# PowerBoard.net
KiCad netlist of a schematic drawn in Altium Designer
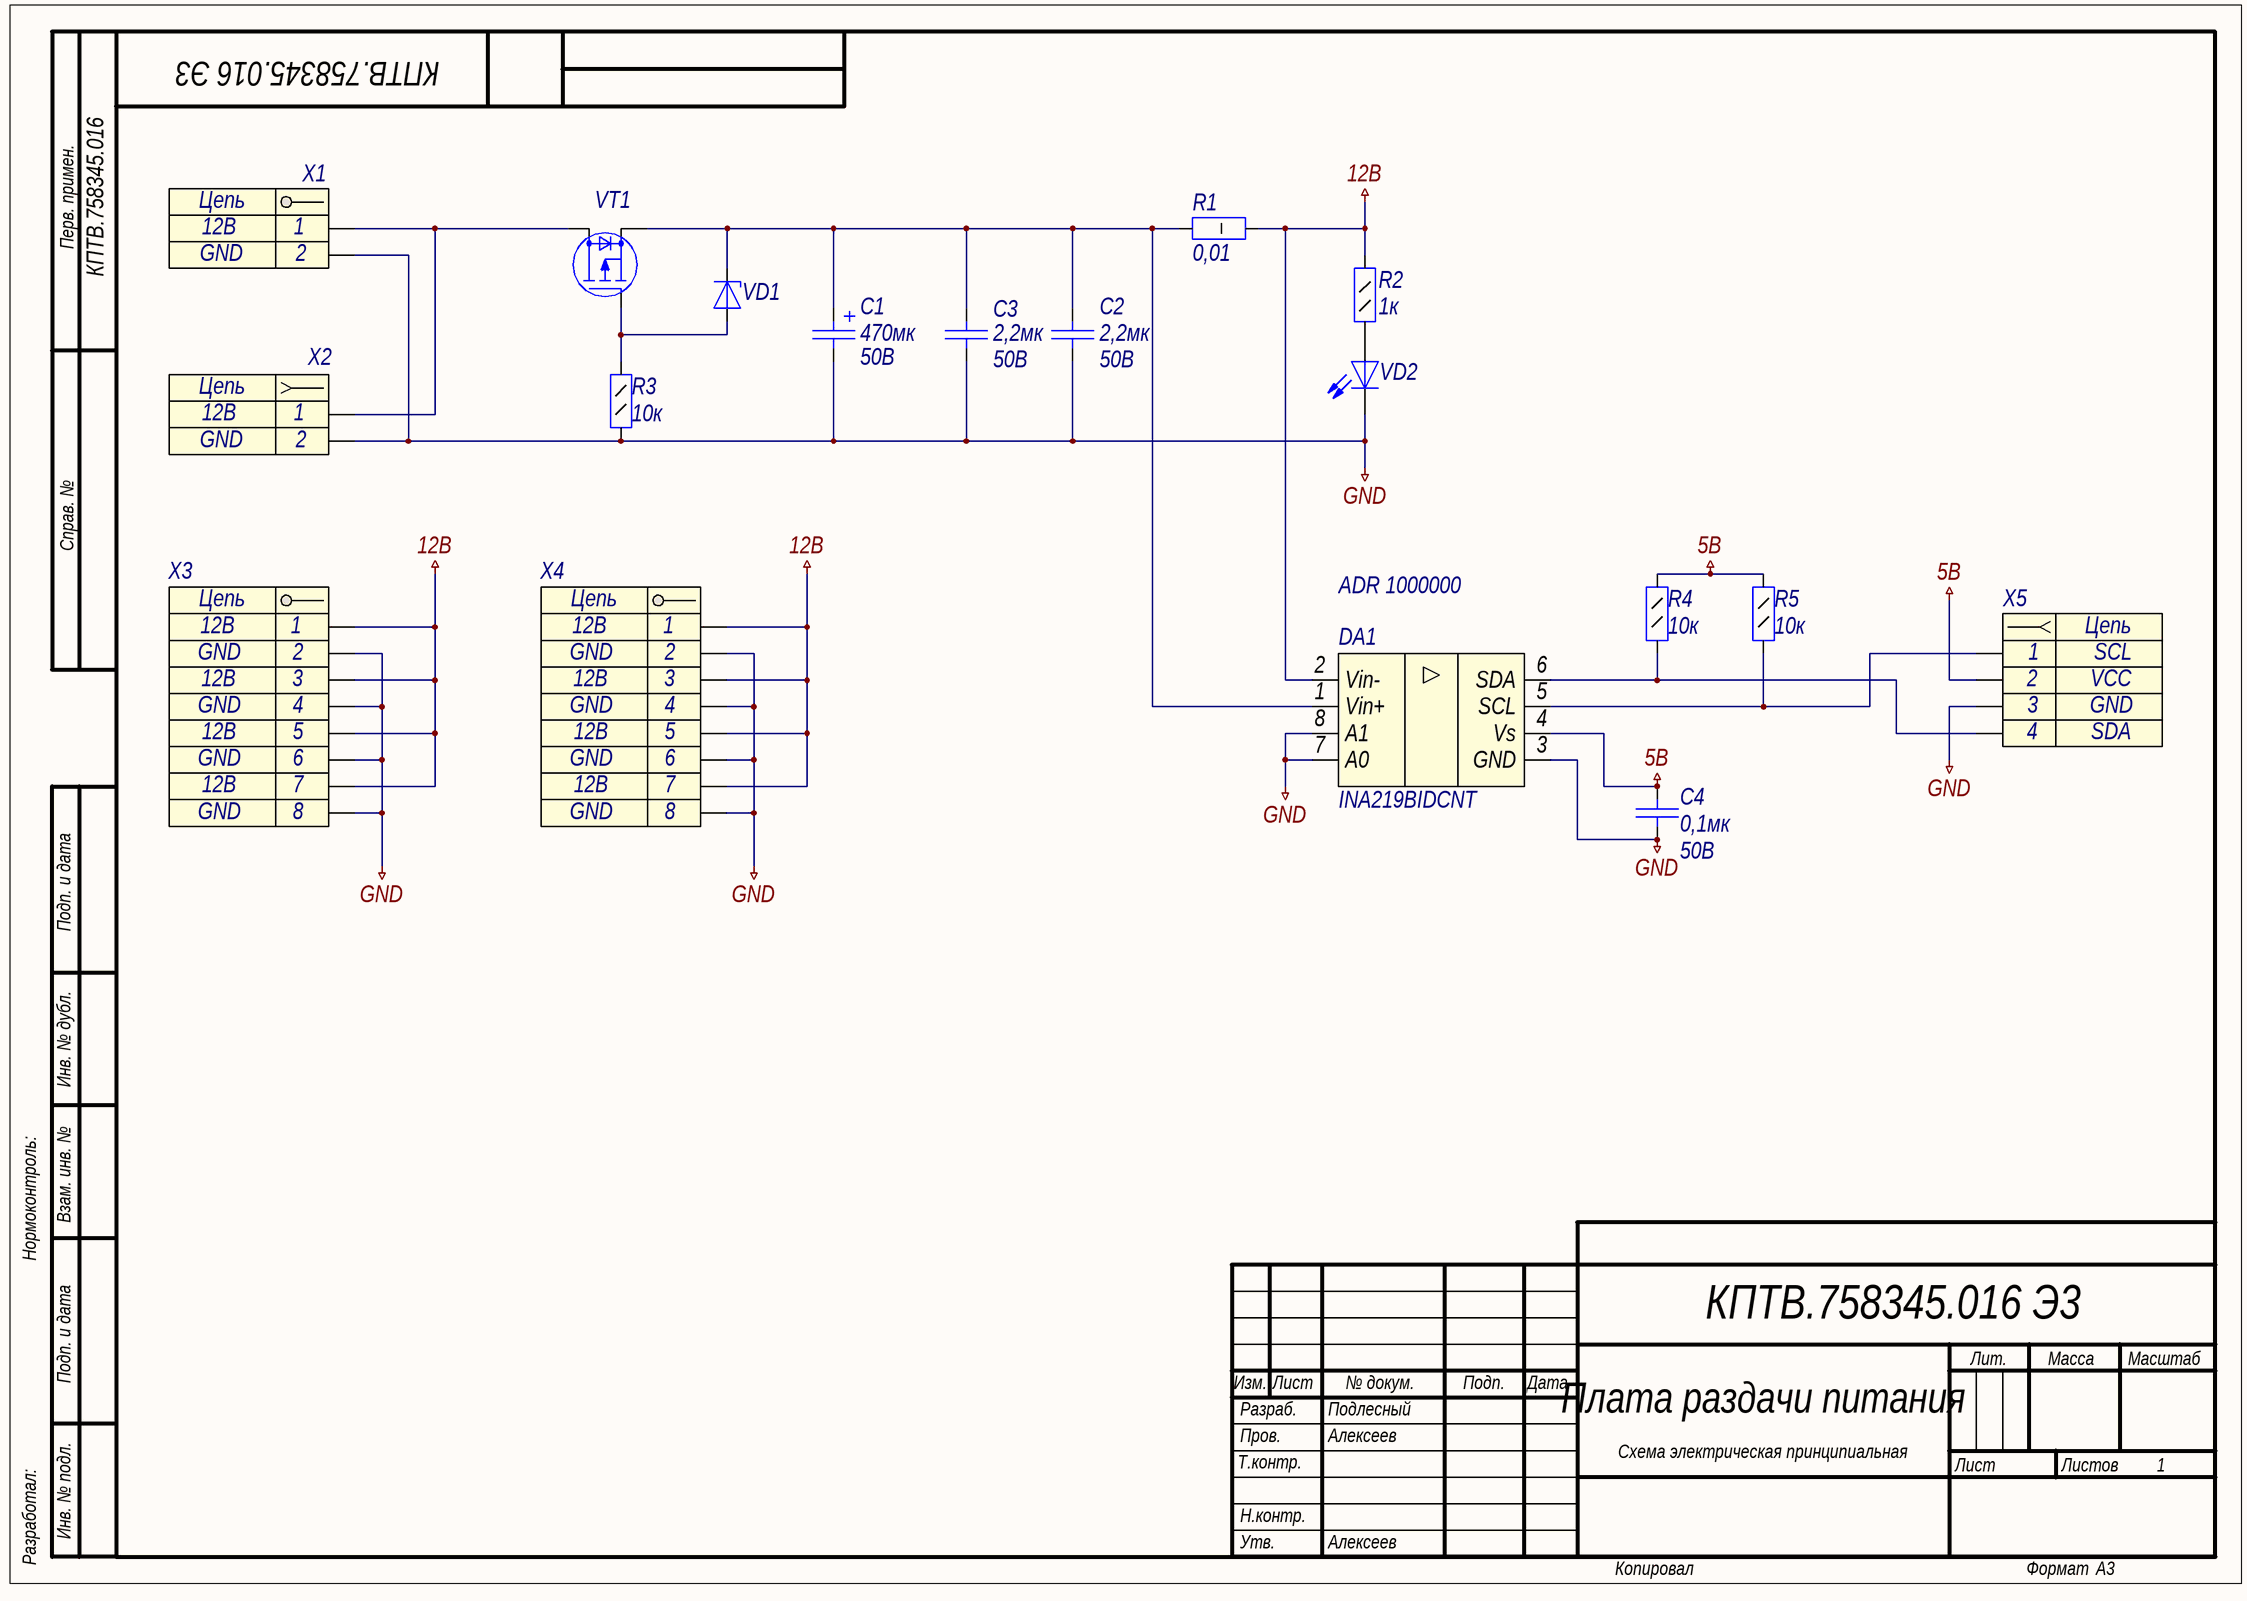
[diagram p0: PowerBoard.schdoc]

(export (version "E")
  (design (tool "Eeschema 10.0.6"))
  (components
    (comp (ref "C1")
      (value "470мк")
      (footprint "K50-35(10X20)_V")
      (description "Конденсатор полярный")
      (fields
        (field (name "VOLTAGE") "50В")
        (field (name "PART NUMBER") "TKR471M1HG20")
        (field (name "Comment") "Capacitor_pol")
      )
      (libsource (lib "MOP44") (part "Capacitor_pol"))
    )
    (comp (ref "C2")
      (value "2,2мк")
      (footprint "C1206")
      (description "Конденсатор")
      (fields
        (field (name "VOLTAGE") "50В")
        (field (name "PART NUMBER") "GRM31CR71H225KA88**L")
        (field (name "Comment") "Capacitor")
      )
      (libsource (lib "MOP44") (part "Capacitor"))
    )
    (comp (ref "C3")
      (value "2,2мк")
      (footprint "C1206")
      (description "Конденсатор")
      (fields
        (field (name "VOLTAGE") "50В")
        (field (name "PART NUMBER") "GRM31CR71H225KA88**L")
        (field (name "Comment") "Capacitor")
      )
      (libsource (lib "MOP44") (part "Capacitor"))
    )
    (comp (ref "C4")
      (value "0,1мк")
      (footprint "C0805")
      (description "Конденсатор")
      (fields
        (field (name "VOLTAGE") "50В")
        (field (name "PART NUMBER") "GRM21BR71H104KA01L ")
        (field (name "Comment") "Capacitor")
      )
      (libsource (lib "MOP44") (part "Capacitor"))
    )
    (comp (ref "DA1")
      (value "INA219BIDCNT")
      (footprint "SOT23-8")
      (description "Токочувствительный усилитель")
      (libsource (lib "MOP44") (part "INA219BIDCNT"))
    )
    (comp (ref "R1")
      (value "0,01")
      (footprint "R2512")
      (description "Резистор")
      (fields (field (name "PART NUMBER") "RL2512FK-070R01L") (field (name "POWER") "1Вт"))
      (libsource (lib "MOP44") (part "Resistor_1Вт"))
    )
    (comp (ref "R2")
      (value "1к")
      (footprint "R0805")
      (description "Резистор")
      (fields (field (name "PART NUMBER") "RC0805FR-071KL") (field (name "POWER") "0,125Вт"))
      (libsource (lib "MOP44") (part "Resistor_0,125Вт"))
    )
    (comp (ref "R3")
      (value "10к")
      (footprint "R0805")
      (description "Резистор")
      (fields (field (name "POWER") "0,125Вт") (field (name "Comment") "Resistor_0,125Вт"))
      (libsource (lib "") (part "Resistor_0,125Вт_1"))
    )
    (comp (ref "R4")
      (value "10к")
      (footprint "R0805")
      (description "Резистор")
      (fields (field (name "POWER") "0,125Вт") (field (name "Comment") "Resistor_0,125Вт"))
      (libsource (lib "") (part "Resistor_0,125Вт_1"))
    )
    (comp (ref "R5")
      (value "10к")
      (footprint "R0805")
      (description "Резистор")
      (fields (field (name "POWER") "0,125Вт") (field (name "Comment") "Resistor_0,125Вт"))
      (libsource (lib "") (part "Resistor_0,125Вт_1"))
    )
    (comp (ref "VD1")
      (value "DiodeZener")
      (footprint "SMA")
      (description "Cтабилитрон (лавинный выпрямительный диод) односторонний")
      (fields (field (name "PART NUMBER") "SMAJ12A"))
      (libsource (lib "MOP44") (part "DiodeZener"))
    )
    (comp (ref "VD2")
      (value "LED")
      (footprint "L_0805")
      (description "Светодиод")
      (fields (field (name "PART NUMBER") "KP-2012EC"))
      (libsource (lib "MOP44") (part "LED"))
    )
    (comp (ref "VT1")
      (value "P-MOSFET")
      (footprint "DPAK")
      (description "N-MOSFET")
      (fields (field (name "PART NUMBER") "FDD6637") (field (name "MANUFACTURER") "Fairchild Semiconductor"))
      (libsource (lib "MOP44") (part "P-MOSFET"))
    )
    (comp (ref "X1")
      (value "Header_2_trm")
      (footprint "TERMINAL-2WAY-5MM")
      (description "Разъем - 2 конт. клеммник")
      (libsource (lib "MOP44") (part "Header_2_trm"))
    )
    (comp (ref "X2")
      (value "Header_2_sct")
      (footprint "XT60-F")
      (description "Разъем - 2 конт. розетка")
      (fields (field (name "PART NUMBER") "XT60-F.G2.Y"))
      (libsource (lib "MOP44") (part "Header_2_sct"))
    )
    (comp (ref "X3")
      (value "Header_8_trm")
      (footprint "TERMINAL-8WAY-3.5MM")
      (description "Разъем - 8 конт. вилка")
      (libsource (lib "MOP44") (part "Header_8_trm"))
    )
    (comp (ref "X4")
      (value "Header_8_trm")
      (footprint "TERMINAL-8WAY-3.5MM_")
      (description "Разъем - 8 конт. вилка")
      (libsource (lib "MOP44") (part "Header_8_trm"))
    )
    (comp (ref "X5")
      (value "Header_4_sct")
      (footprint "69254-002LF")
      (description "Разъем - 4 конт. розетка")
      (fields (field (name "PART NUMBER") "69254-002LF"))
      (libsource (lib "MOP44") (part "Header_4_sct"))
    )
  )
  (nets
    (net (code "1") (name "5B") (class "Default")
      (node (ref "C4") (pin "2") (pinfunction "2_2") (pintype "passive"))
      (node (ref "DA1") (pin "4") (pinfunction "Vs_4") (pintype "passive"))
      (node (ref "R4") (pin "1") (pinfunction "1_1") (pintype "passive"))
      (node (ref "R5") (pin "1") (pinfunction "1_1") (pintype "passive"))
      (node (ref "X5") (pin "2") (pinfunction "2_2") (pintype "passive"))
    )
    (net (code "2") (name "12B") (class "Default")
      (node (ref "DA1") (pin "2") (pinfunction "Vin-_2") (pintype "passive"))
      (node (ref "R1") (pin "2") (pinfunction "5_2") (pintype "passive"))
      (node (ref "R2") (pin "2") (pinfunction "2_2") (pintype "passive"))
      (node (ref "X3") (pin "1") (pinfunction "1_1") (pintype "passive"))
      (node (ref "X3") (pin "3") (pinfunction "3_3") (pintype "passive"))
      (node (ref "X3") (pin "5") (pinfunction "5_5") (pintype "passive"))
      (node (ref "X3") (pin "7") (pinfunction "7_7") (pintype "passive"))
      (node (ref "X4") (pin "1") (pinfunction "1_1") (pintype "passive"))
      (node (ref "X4") (pin "3") (pinfunction "3_3") (pintype "passive"))
      (node (ref "X4") (pin "5") (pinfunction "5_5") (pintype "passive"))
      (node (ref "X4") (pin "7") (pinfunction "7_7") (pintype "passive"))
    )
    (net (code "3") (name "GND") (class "Default")
      (node (ref "C1") (pin "2") (pinfunction "2_2") (pintype "passive"))
      (node (ref "C2") (pin "1") (pinfunction "1_1") (pintype "passive"))
      (node (ref "C3") (pin "1") (pinfunction "1_1") (pintype "passive"))
      (node (ref "C4") (pin "1") (pinfunction "1_1") (pintype "passive"))
      (node (ref "DA1") (pin "3") (pinfunction "GND_3") (pintype "passive"))
      (node (ref "DA1") (pin "7") (pinfunction "A0_7") (pintype "passive"))
      (node (ref "DA1") (pin "8") (pinfunction "A1_8") (pintype "passive"))
      (node (ref "R3") (pin "2") (pinfunction "2_2") (pintype "passive"))
      (node (ref "VD2") (pin "1") (pinfunction "K_1") (pintype "passive"))
      (node (ref "X1") (pin "2") (pinfunction "2_2") (pintype "passive"))
      (node (ref "X2") (pin "2") (pinfunction "2_2") (pintype "passive"))
      (node (ref "X3") (pin "2") (pinfunction "2_2") (pintype "passive"))
      (node (ref "X3") (pin "4") (pinfunction "4_4") (pintype "passive"))
      (node (ref "X3") (pin "6") (pinfunction "6_6") (pintype "passive"))
      (node (ref "X3") (pin "8") (pinfunction "8_8") (pintype "passive"))
      (node (ref "X4") (pin "2") (pinfunction "2_2") (pintype "passive"))
      (node (ref "X4") (pin "4") (pinfunction "4_4") (pintype "passive"))
      (node (ref "X4") (pin "6") (pinfunction "6_6") (pintype "passive"))
      (node (ref "X4") (pin "8") (pinfunction "8_8") (pintype "passive"))
      (node (ref "X5") (pin "3") (pinfunction "3_3") (pintype "passive"))
    )
    (net (code "4") (name "Net-(DA1-SCL)") (class "Default")
      (node (ref "DA1") (pin "5") (pinfunction "SCL_5") (pintype "passive"))
      (node (ref "R5") (pin "2") (pinfunction "2_2") (pintype "passive"))
      (node (ref "X5") (pin "1") (pinfunction "1_1") (pintype "passive"))
    )
    (net (code "5") (name "Net-(DA1-SDA)") (class "Default")
      (node (ref "DA1") (pin "6") (pinfunction "SDA_6") (pintype "passive"))
      (node (ref "R4") (pin "2") (pinfunction "2_2") (pintype "passive"))
      (node (ref "X5") (pin "4") (pinfunction "4_4") (pintype "passive"))
    )
    (net (code "6") (name "Net-(DA1-Vin+)") (class "Default")
      (node (ref "C1") (pin "1") (pinfunction "1_1") (pintype "passive"))
      (node (ref "C2") (pin "2") (pinfunction "2_2") (pintype "passive"))
      (node (ref "C3") (pin "2") (pinfunction "2_2") (pintype "passive"))
      (node (ref "DA1") (pin "1") (pinfunction "Vin+_1") (pintype "passive"))
      (node (ref "R1") (pin "1") (pinfunction "1_1") (pintype "passive"))
      (node (ref "VD1") (pin "1") (pinfunction "K_1") (pintype "passive"))
      (node (ref "VT1") (pin "3") (pinfunction "S_3") (pintype "passive"))
    )
    (net (code "7") (name "Net-(VD1-A)") (class "Default")
      (node (ref "R3") (pin "1") (pinfunction "1_1") (pintype "passive"))
      (node (ref "VD1") (pin "2") (pinfunction "A_2") (pintype "passive"))
      (node (ref "VT1") (pin "1") (pinfunction "G_1") (pintype "passive"))
    )
    (net (code "8") (name "Net-(VD2-A)") (class "Default")
      (node (ref "R2") (pin "1") (pinfunction "1_1") (pintype "passive"))
      (node (ref "VD2") (pin "2") (pinfunction "A_2") (pintype "passive"))
    )
    (net (code "9") (name "Net-(VT1-D)") (class "Default")
      (node (ref "VT1") (pin "2") (pinfunction "D_2") (pintype "passive"))
      (node (ref "X1") (pin "1") (pinfunction "1_1") (pintype "passive"))
      (node (ref "X2") (pin "1") (pinfunction "1_1") (pintype "passive"))
    )
  )
)
